# Schematic.net
KiCad netlist of a schematic drawn in EAGLE
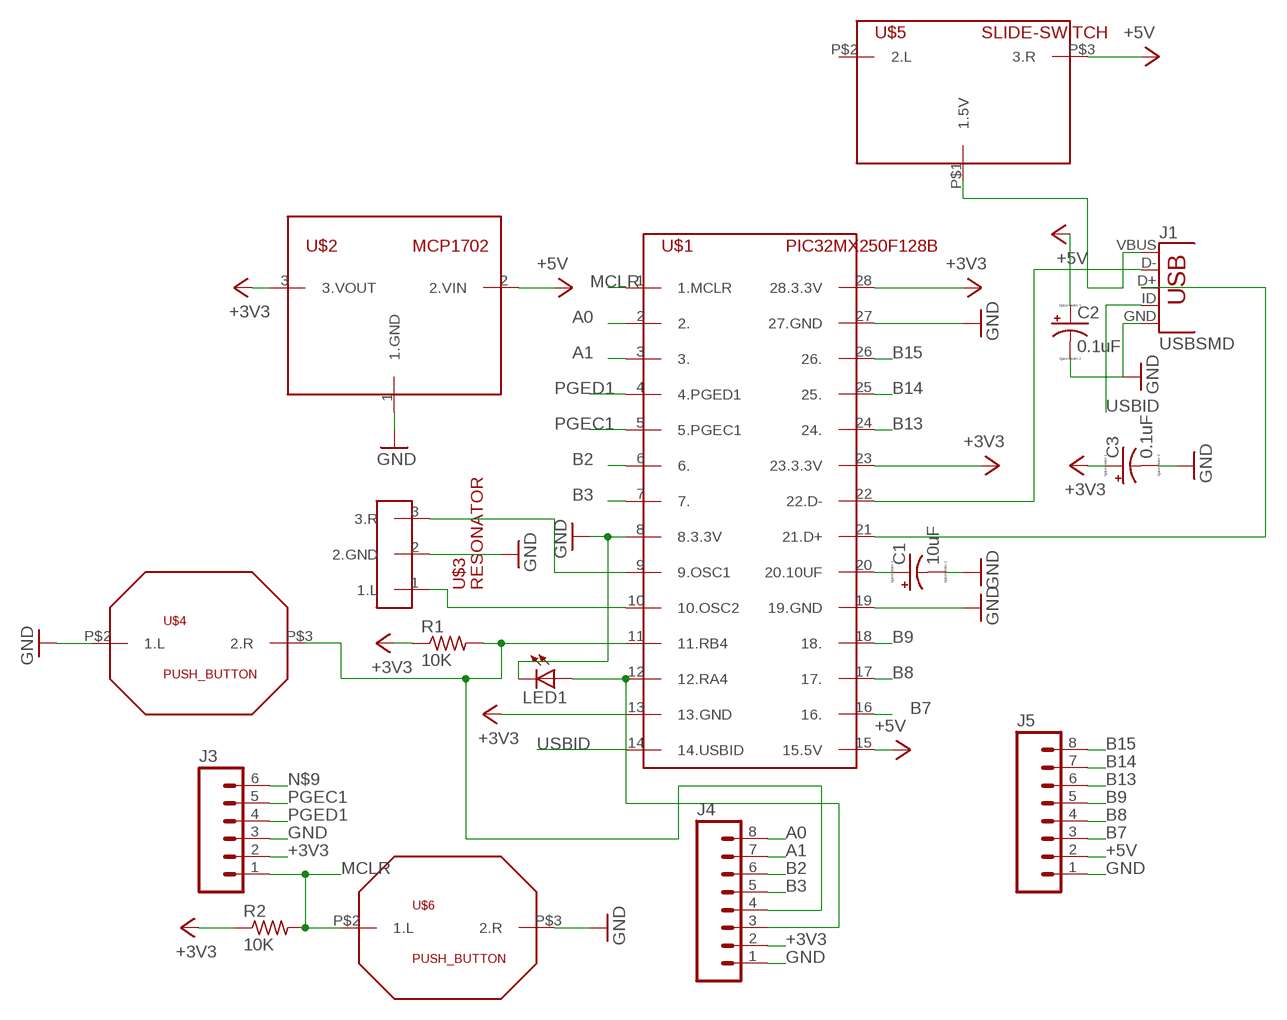
[diagram p0: schematic, sheet 1]

(export (version "E")
  (design (tool "Eeschema 10.0.6"))
  (components
    (comp (ref "C1")
      (value "10uF")
      (footprint "eagle-import:E2,5-5")
      (libsource (lib "eagle-import") (part "CPOL-USE2.5-5"))
    )
    (comp (ref "C2")
      (value "0.1uF")
      (footprint "eagle-import:E2,5-5")
      (libsource (lib "eagle-import") (part "CPOL-USE2.5-5"))
    )
    (comp (ref "C3")
      (value "0.1uF")
      (footprint "eagle-import:E2,5-5")
      (libsource (lib "eagle-import") (part "CPOL-USE2.5-5"))
    )
    (comp (ref "J1")
      (value "USBSMD")
      (footprint "eagle-import:USB-MINIB")
      (libsource (lib "eagle-import") (part "USBSMD"))
    )
    (comp (ref "J3")
      (value "M06SILK_FEMALE_PTH")
      (footprint "eagle-import:1X06")
      (libsource (lib "eagle-import") (part "M06SILK_FEMALE_PTH"))
    )
    (comp (ref "J4")
      (value "M08SILK_FEMALE_PTH")
      (footprint "eagle-import:1X08")
      (libsource (lib "eagle-import") (part "M08SILK_FEMALE_PTH"))
    )
    (comp (ref "J5")
      (value "M08SILK_FEMALE_PTH")
      (footprint "eagle-import:1X08")
      (libsource (lib "eagle-import") (part "M08SILK_FEMALE_PTH"))
    )
    (comp (ref "LED1")
      (value "LED3MM")
      (footprint "eagle-import:LED3MM")
      (libsource (lib "eagle-import") (part "LED3MM"))
    )
    (comp (ref "R1")
      (value "10K")
      (footprint "eagle-import:0207_10")
      (libsource (lib "eagle-import") (part "R-US_0207/10"))
    )
    (comp (ref "R2")
      (value "10K")
      (footprint "eagle-import:0207_10")
      (libsource (lib "eagle-import") (part "R-US_0207/10"))
    )
    (comp (ref "U$1")
      (value "PIC32MX250F128B")
      (footprint "eagle-import:DIL28-3")
      (libsource (lib "eagle-import") (part "PIC32MX250F128B"))
    )
    (comp (ref "U$2")
      (value "MCP1702")
      (footprint "eagle-import:TO92")
      (libsource (lib "eagle-import") (part "MCP1702"))
    )
    (comp (ref "U$3")
      (value "RESONATOR")
      (footprint "eagle-import:1X03")
      (libsource (lib "eagle-import") (part "RESONATOR"))
    )
    (comp (ref "U$4")
      (value "PUSH_BUTTON")
      (footprint "eagle-import:PUSH_BUTTON")
      (libsource (lib "eagle-import") (part "PUSH_BUTTON"))
    )
    (comp (ref "U$5")
      (value "SLIDE-SWITCH")
      (footprint "eagle-import:SLIDE-SWITCH")
      (libsource (lib "eagle-import") (part "SLIDE-SWITCH"))
    )
    (comp (ref "U$6")
      (value "PUSH_BUTTON")
      (footprint "eagle-import:PUSH_BUTTON")
      (libsource (lib "eagle-import") (part "PUSH_BUTTON"))
    )
  )
  (nets
    (net (code "1") (name "+3V3") (class "Default")
      (node (ref "C3") (pin "+") (pinfunction "+_+") (pintype "passive"))
      (node (ref "J3") (pin "2") (pinfunction "2_2") (pintype "passive"))
      (node (ref "J4") (pin "2") (pinfunction "2_2") (pintype "passive"))
      (node (ref "R1") (pin "1") (pinfunction "1_1") (pintype "passive"))
      (node (ref "R2") (pin "1") (pinfunction "1_1") (pintype "passive"))
      (node (ref "U$1") (pin "13") (pinfunction "13.GND_13") (pintype "bidirectional"))
      (node (ref "U$1") (pin "23") (pinfunction "23.3.3V_23") (pintype "bidirectional"))
      (node (ref "U$1") (pin "28") (pinfunction "28.3.3V_28") (pintype "bidirectional"))
      (node (ref "U$2") (pin "3") (pinfunction "3.VOUT_3") (pintype "bidirectional"))
    )
    (net (code "2") (name "+5V") (class "Default")
      (node (ref "C2") (pin "+") (pinfunction "+_+") (pintype "passive"))
      (node (ref "J5") (pin "2") (pinfunction "2_2") (pintype "passive"))
      (node (ref "U$1") (pin "15") (pinfunction "15.5V_15") (pintype "bidirectional"))
      (node (ref "U$2") (pin "2") (pinfunction "2.VIN_2") (pintype "bidirectional"))
      (node (ref "U$5") (pin "P$3") (pinfunction "3.R_P$3") (pintype "bidirectional"))
    )
    (net (code "3") (name "/A0") (class "Default")
      (node (ref "J4") (pin "8") (pinfunction "8_8") (pintype "passive"))
      (node (ref "U$1") (pin "2") (pinfunction "2._2") (pintype "bidirectional"))
    )
    (net (code "4") (name "/A1") (class "Default")
      (node (ref "J4") (pin "7") (pinfunction "7_7") (pintype "passive"))
      (node (ref "U$1") (pin "3") (pinfunction "3._3") (pintype "bidirectional"))
    )
    (net (code "5") (name "/B2") (class "Default")
      (node (ref "J4") (pin "6") (pinfunction "6_6") (pintype "passive"))
      (node (ref "U$1") (pin "6") (pinfunction "6._6") (pintype "bidirectional"))
    )
    (net (code "6") (name "/B3") (class "Default")
      (node (ref "J4") (pin "5") (pinfunction "5_5") (pintype "passive"))
      (node (ref "U$1") (pin "7") (pinfunction "7._7") (pintype "bidirectional"))
    )
    (net (code "7") (name "/B7") (class "Default")
      (node (ref "J5") (pin "3") (pinfunction "3_3") (pintype "passive"))
      (node (ref "U$1") (pin "16") (pinfunction "16._16") (pintype "bidirectional"))
    )
    (net (code "8") (name "/B8") (class "Default")
      (node (ref "J5") (pin "4") (pinfunction "4_4") (pintype "passive"))
      (node (ref "U$1") (pin "17") (pinfunction "17._17") (pintype "bidirectional"))
    )
    (net (code "9") (name "/B9") (class "Default")
      (node (ref "J5") (pin "5") (pinfunction "5_5") (pintype "passive"))
      (node (ref "U$1") (pin "18") (pinfunction "18._18") (pintype "bidirectional"))
    )
    (net (code "10") (name "/B13") (class "Default")
      (node (ref "J5") (pin "6") (pinfunction "6_6") (pintype "passive"))
      (node (ref "U$1") (pin "24") (pinfunction "24._24") (pintype "bidirectional"))
    )
    (net (code "11") (name "/B14") (class "Default")
      (node (ref "J5") (pin "7") (pinfunction "7_7") (pintype "passive"))
      (node (ref "U$1") (pin "25") (pinfunction "25._25") (pintype "bidirectional"))
    )
    (net (code "12") (name "/B15") (class "Default")
      (node (ref "J5") (pin "8") (pinfunction "8_8") (pintype "passive"))
      (node (ref "U$1") (pin "26") (pinfunction "26._26") (pintype "bidirectional"))
    )
    (net (code "13") (name "/MCLR") (class "Default")
      (node (ref "J3") (pin "1") (pinfunction "1_1") (pintype "passive"))
      (node (ref "R2") (pin "2") (pinfunction "2_2") (pintype "passive"))
      (node (ref "U$1") (pin "1") (pinfunction "1.MCLR_1") (pintype "bidirectional"))
      (node (ref "U$6") (pin "P$2") (pinfunction "1.L_P$2") (pintype "bidirectional"))
    )
    (net (code "14") (name "/N$9") (class "Default")
      (node (ref "J3") (pin "6") (pinfunction "6_6") (pintype "passive"))
    )
    (net (code "15") (name "/PGEC1") (class "Default")
      (node (ref "J3") (pin "5") (pinfunction "5_5") (pintype "passive"))
      (node (ref "U$1") (pin "5") (pinfunction "5.PGEC1_5") (pintype "bidirectional"))
    )
    (net (code "16") (name "/PGED1") (class "Default")
      (node (ref "J3") (pin "4") (pinfunction "4_4") (pintype "passive"))
      (node (ref "U$1") (pin "4") (pinfunction "4.PGED1_4") (pintype "bidirectional"))
    )
    (net (code "17") (name "/USBID") (class "Default")
      (node (ref "J1") (pin "ID") (pinfunction "2.ID_ID") (pintype "bidirectional"))
      (node (ref "U$1") (pin "14") (pinfunction "14.USBID_14") (pintype "bidirectional"))
    )
    (net (code "18") (name "GND") (class "Default")
      (node (ref "C1") (pin "-") (pinfunction "-_-") (pintype "passive"))
      (node (ref "C2") (pin "-") (pinfunction "-_-") (pintype "passive"))
      (node (ref "C3") (pin "-") (pinfunction "-_-") (pintype "passive"))
      (node (ref "J1") (pin "GND") (pinfunction "1.GND_GND") (pintype "bidirectional"))
      (node (ref "J3") (pin "3") (pinfunction "3_3") (pintype "passive"))
      (node (ref "J4") (pin "1") (pinfunction "1_1") (pintype "passive"))
      (node (ref "J5") (pin "1") (pinfunction "1_1") (pintype "passive"))
      (node (ref "LED1") (pin "K") (pinfunction "C_K") (pintype "passive"))
      (node (ref "U$1") (pin "19") (pinfunction "19.GND_19") (pintype "bidirectional"))
      (node (ref "U$1") (pin "27") (pinfunction "27.GND_27") (pintype "bidirectional"))
      (node (ref "U$1") (pin "8") (pinfunction "8.3.3V_8") (pintype "bidirectional"))
      (node (ref "U$2") (pin "1") (pinfunction "1.GND_1") (pintype "bidirectional"))
      (node (ref "U$3") (pin "2") (pinfunction "2.GND_2") (pintype "bidirectional"))
      (node (ref "U$4") (pin "P$2") (pinfunction "1.L_P$2") (pintype "bidirectional"))
      (node (ref "U$6") (pin "P$3") (pinfunction "2.R_P$3") (pintype "bidirectional"))
    )
    (net (code "19") (name "Net-(J1-3.D+)") (class "Default")
      (node (ref "J1") (pin "D+") (pinfunction "3.D+_D+") (pintype "bidirectional"))
      (node (ref "U$1") (pin "21") (pinfunction "21.D+_21") (pintype "bidirectional"))
    )
    (net (code "20") (name "Net-(J1-4.D-)") (class "Default")
      (node (ref "J1") (pin "D-") (pinfunction "4.D-_D-") (pintype "bidirectional"))
      (node (ref "U$1") (pin "22") (pinfunction "22.D-_22") (pintype "bidirectional"))
    )
    (net (code "21") (name "Net-(J1-5.VBUS)") (class "Default")
      (node (ref "J1") (pin "VBUS") (pinfunction "5.VBUS_VBUS") (pintype "bidirectional"))
      (node (ref "U$5") (pin "P$1") (pinfunction "1.5V_P$1") (pintype "bidirectional"))
    )
    (net (code "22") (name "Net-(U$1-9.OSC1)") (class "Default")
      (node (ref "U$1") (pin "9") (pinfunction "9.OSC1_9") (pintype "bidirectional"))
      (node (ref "U$3") (pin "3") (pinfunction "3.R_3") (pintype "bidirectional"))
    )
    (net (code "23") (name "Net-(U$1-10.OSC2)") (class "Default")
      (node (ref "U$1") (pin "10") (pinfunction "10.OSC2_10") (pintype "bidirectional"))
      (node (ref "U$3") (pin "1") (pinfunction "1.L_1") (pintype "bidirectional"))
    )
    (net (code "24") (name "Net-(U$1-11.RB4)") (class "Default")
      (node (ref "J4") (pin "4") (pinfunction "4_4") (pintype "passive"))
      (node (ref "R1") (pin "2") (pinfunction "2_2") (pintype "passive"))
      (node (ref "U$1") (pin "11") (pinfunction "11.RB4_11") (pintype "bidirectional"))
      (node (ref "U$4") (pin "P$3") (pinfunction "2.R_P$3") (pintype "bidirectional"))
    )
    (net (code "25") (name "Net-(U$1-12.RA4)") (class "Default")
      (node (ref "J4") (pin "3") (pinfunction "3_3") (pintype "passive"))
      (node (ref "LED1") (pin "A") (pinfunction "A_A") (pintype "passive"))
      (node (ref "U$1") (pin "12") (pinfunction "12.RA4_12") (pintype "bidirectional"))
    )
    (net (code "26") (name "Net-(U$1-20.10UF)") (class "Default")
      (node (ref "C1") (pin "+") (pinfunction "+_+") (pintype "passive"))
      (node (ref "U$1") (pin "20") (pinfunction "20.10UF_20") (pintype "bidirectional"))
    )
    (net (code "27") (name "unconnected-(U$5-2.L-PadP$2)") (class "Default")
      (node (ref "U$5") (pin "P$2") (pinfunction "2.L_P$2") (pintype "bidirectional"))
    )
  )
)
